# SMPS_3V3.net
KiCad netlist of a schematic drawn in Altium Designer
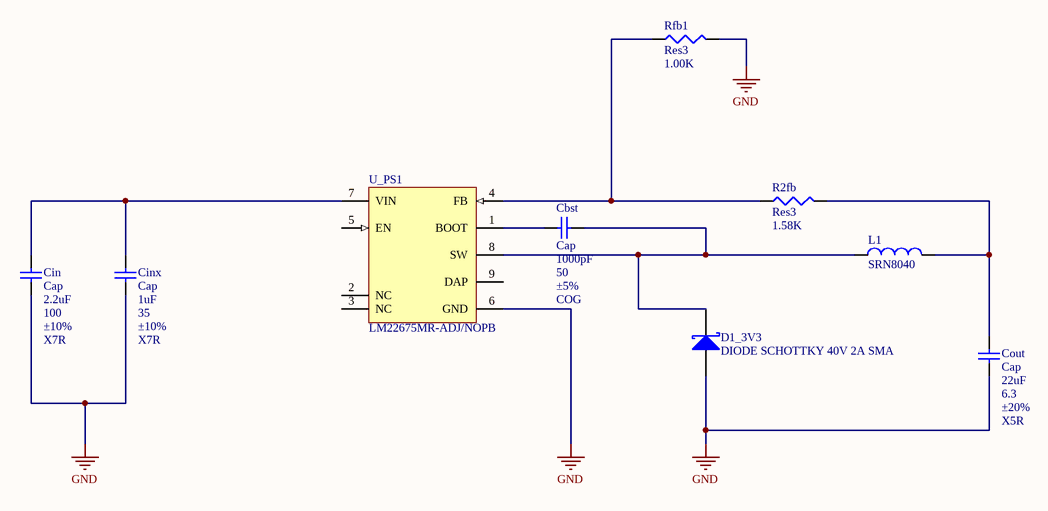
[diagram p0: SMPS_3V3.SchDoc]

(export (version "E")
  (design (tool "Eeschema 10.0.6"))
  (components
    (comp (ref "Cbst")
      (value "Cap")
      (footprint "CAPC2012X09M")
      (description "CAP CER 1000pF 50v COG 0805")
      (fields
        (field (name "ALTIUM_VALUE") "1000pF")
        (field (name "WV") "50")
        (field (name "TOLERANCE") "±5%")
        (field (name "TYPE") "COG")
        (field (name "MPN") "C0805C102J5GACTU")
      )
      (libsource (lib "esd_library") (part "CAP-COG-1000pF-50V-±5%"))
    )
    (comp (ref "Cin")
      (value "Cap")
      (footprint "C1210")
      (description "CAP CER 2.2uF 100v X7R 1210")
      (fields
        (field (name "ALTIUM_VALUE") "2.2uF")
        (field (name "WV") "100")
        (field (name "TOLERANCE") "±10%")
        (field (name "TYPE") "X7R")
        (field (name "MPN") "C0805C225K4RACTU")
      )
      (libsource (lib "esd_library") (part "CAP-X7R-2.2uF-16V-±10%"))
    )
    (comp (ref "Cinx")
      (value "Cap")
      (footprint "CAPC2012X09M")
      (description "CAP CER 1uF 35v X7R 0805")
      (fields
        (field (name "ALTIUM_VALUE") "1uF")
        (field (name "WV") "35")
        (field (name "TOLERANCE") "±10%")
        (field (name "TYPE") "X7R")
        (field (name "MPN") "C0805C105K4RACTU")
      )
      (libsource (lib "esd_library") (part "CAP-X7R-1uF-16V-±10%"))
    )
    (comp (ref "Cout")
      (value "Cap")
      (footprint "CAPC2012X09M")
      (description "CAP CER 22uF 6.3v X5R 0805")
      (fields
        (field (name "ALTIUM_VALUE") "22uF")
        (field (name "WV") "6.3")
        (field (name "TOLERANCE") "±20%")
        (field (name "TYPE") "X5R")
        (field (name "MPN") "C0805C226M9PACTU")
      )
      (libsource (lib "esd_library") (part "CAP-X5R-22uF-6.3V-±20%"))
    )
    (comp (ref "D1_3V3")
      (value "DIODE SCHOTTKY 40V 2A SMA")
      (footprint "DIOM4326X23M")
      (description "Schottky Rectifier")
      (fields (field (name "MPN") "B240A-13-F"))
      (libsource (lib "esd_library") (part "DIODE SCHOTTKY 40V 2A SMA"))
    )
    (comp (ref "L1")
      (value "SRN8040")
      (footprint "INDP8080X40M")
      (description "FIXED IND 22UH 2.2A 100 MOHM SMD")
      (fields (field (name "MPN") "SRN8040-220M"))
      (libsource (lib "esd_library") (part "SRN8040"))
    )
    (comp (ref "R2fb")
      (value "Res3")
      (footprint "RESC2112X05M")
      (description "RES SMD 1.58K OHM 1% 1/8W 0805")
      (fields (field (name "ALTIUM_VALUE") "1.58K") (field (name "MPN") "CRCW08051K58FKEA"))
      (libsource (lib "esd_library") (part "Resistor_1.58K"))
    )
    (comp (ref "Rfb1")
      (value "Res3")
      (footprint "RESC2112X05M")
      (description "RES SMD 1.00K OHM 1% 1/8W 0805")
      (fields (field (name "MPN") "CRCW08051K00FKEA") (field (name "ALTIUM_VALUE") "1.00K"))
      (libsource (lib "esd_library") (part "Resistor_1.00K"))
    )
    (comp (ref "U_PS1")
      (value "LM22675MR-ADJ/NOPB")
      (footprint "MRA08B_L")
      (description "1A SIMPLE SWITCHER®, Step-Down Voltage Regulator with Precision Enable, 8-pin PSOP, Pb-Free")
      (fields
        (field (name "MANUFACTURER") "National Semiconductor")
        (field (name "MPN") "LM22675MRE-ADJ/NOPB")
      )
      (libsource (lib "esd_library") (part "LM22675MR-ADJ/NOPB"))
    )
  )
  (nets
    (net (code "1") (name "GND") (class "Default")
      (node (ref "Cin") (pin "1") (pinfunction "1_1") (pintype "passive"))
      (node (ref "Cinx") (pin "1") (pinfunction "1_1") (pintype "passive"))
      (node (ref "Cout") (pin "1") (pinfunction "1_1") (pintype "passive"))
      (node (ref "D1_3V3") (pin "2") (pinfunction "A_2") (pintype "passive"))
      (node (ref "Rfb1") (pin "2") (pinfunction "2_2") (pintype "passive"))
      (node (ref "U_PS1") (pin "6") (pinfunction "GND_6") (pintype "power_in"))
    )
    (net (code "2") (name "Net-(Cout-Pad2)") (class "Default")
      (node (ref "Cout") (pin "2") (pinfunction "2_2") (pintype "passive"))
      (node (ref "L1") (pin "2") (pinfunction "2_2") (pintype "passive"))
      (node (ref "R2fb") (pin "2") (pinfunction "2_2") (pintype "passive"))
    )
    (net (code "3") (name "Net-(D1_3V3-K)") (class "Default")
      (node (ref "Cbst") (pin "2") (pinfunction "2_2") (pintype "passive"))
      (node (ref "D1_3V3") (pin "1") (pinfunction "K_1") (pintype "passive"))
      (node (ref "L1") (pin "1") (pinfunction "1_1") (pintype "passive"))
      (node (ref "U_PS1") (pin "8") (pinfunction "SW_8") (pintype "power_in"))
    )
    (net (code "4") (name "Net-(U_PS1-BOOT)") (class "Default")
      (node (ref "Cbst") (pin "1") (pinfunction "1_1") (pintype "passive"))
      (node (ref "U_PS1") (pin "1") (pinfunction "BOOT_1") (pintype "passive"))
    )
    (net (code "5") (name "Net-(U_PS1-FB)") (class "Default")
      (node (ref "R2fb") (pin "1") (pinfunction "1_1") (pintype "passive"))
      (node (ref "Rfb1") (pin "1") (pinfunction "1_1") (pintype "passive"))
      (node (ref "U_PS1") (pin "4") (pinfunction "FB_4") (pintype "input"))
    )
    (net (code "6") (name "Net-(U_PS1-VIN)") (class "Default")
      (node (ref "Cin") (pin "2") (pinfunction "2_2") (pintype "passive"))
      (node (ref "Cinx") (pin "2") (pinfunction "2_2") (pintype "passive"))
      (node (ref "U_PS1") (pin "7") (pinfunction "VIN_7") (pintype "power_in"))
    )
    (net (code "7") (name "unconnected-(U_PS1-DAP-Pad9)") (class "Default")
      (node (ref "U_PS1") (pin "9") (pinfunction "DAP_9") (pintype "power_in"))
    )
    (net (code "8") (name "unconnected-(U_PS1-EN-Pad5)") (class "Default")
      (node (ref "U_PS1") (pin "5") (pinfunction "EN_5") (pintype "input"))
    )
    (net (code "9") (name "unconnected-(U_PS1-NC-Pad2)") (class "Default")
      (node (ref "U_PS1") (pin "2") (pinfunction "NC_2") (pintype "passive"))
    )
    (net (code "10") (name "unconnected-(U_PS1-NC-Pad3)") (class "Default")
      (node (ref "U_PS1") (pin "3") (pinfunction "NC_3") (pintype "passive"))
    )
  )
)
